# Schematic.net
KiCad netlist of a schematic drawn in EasyEDA
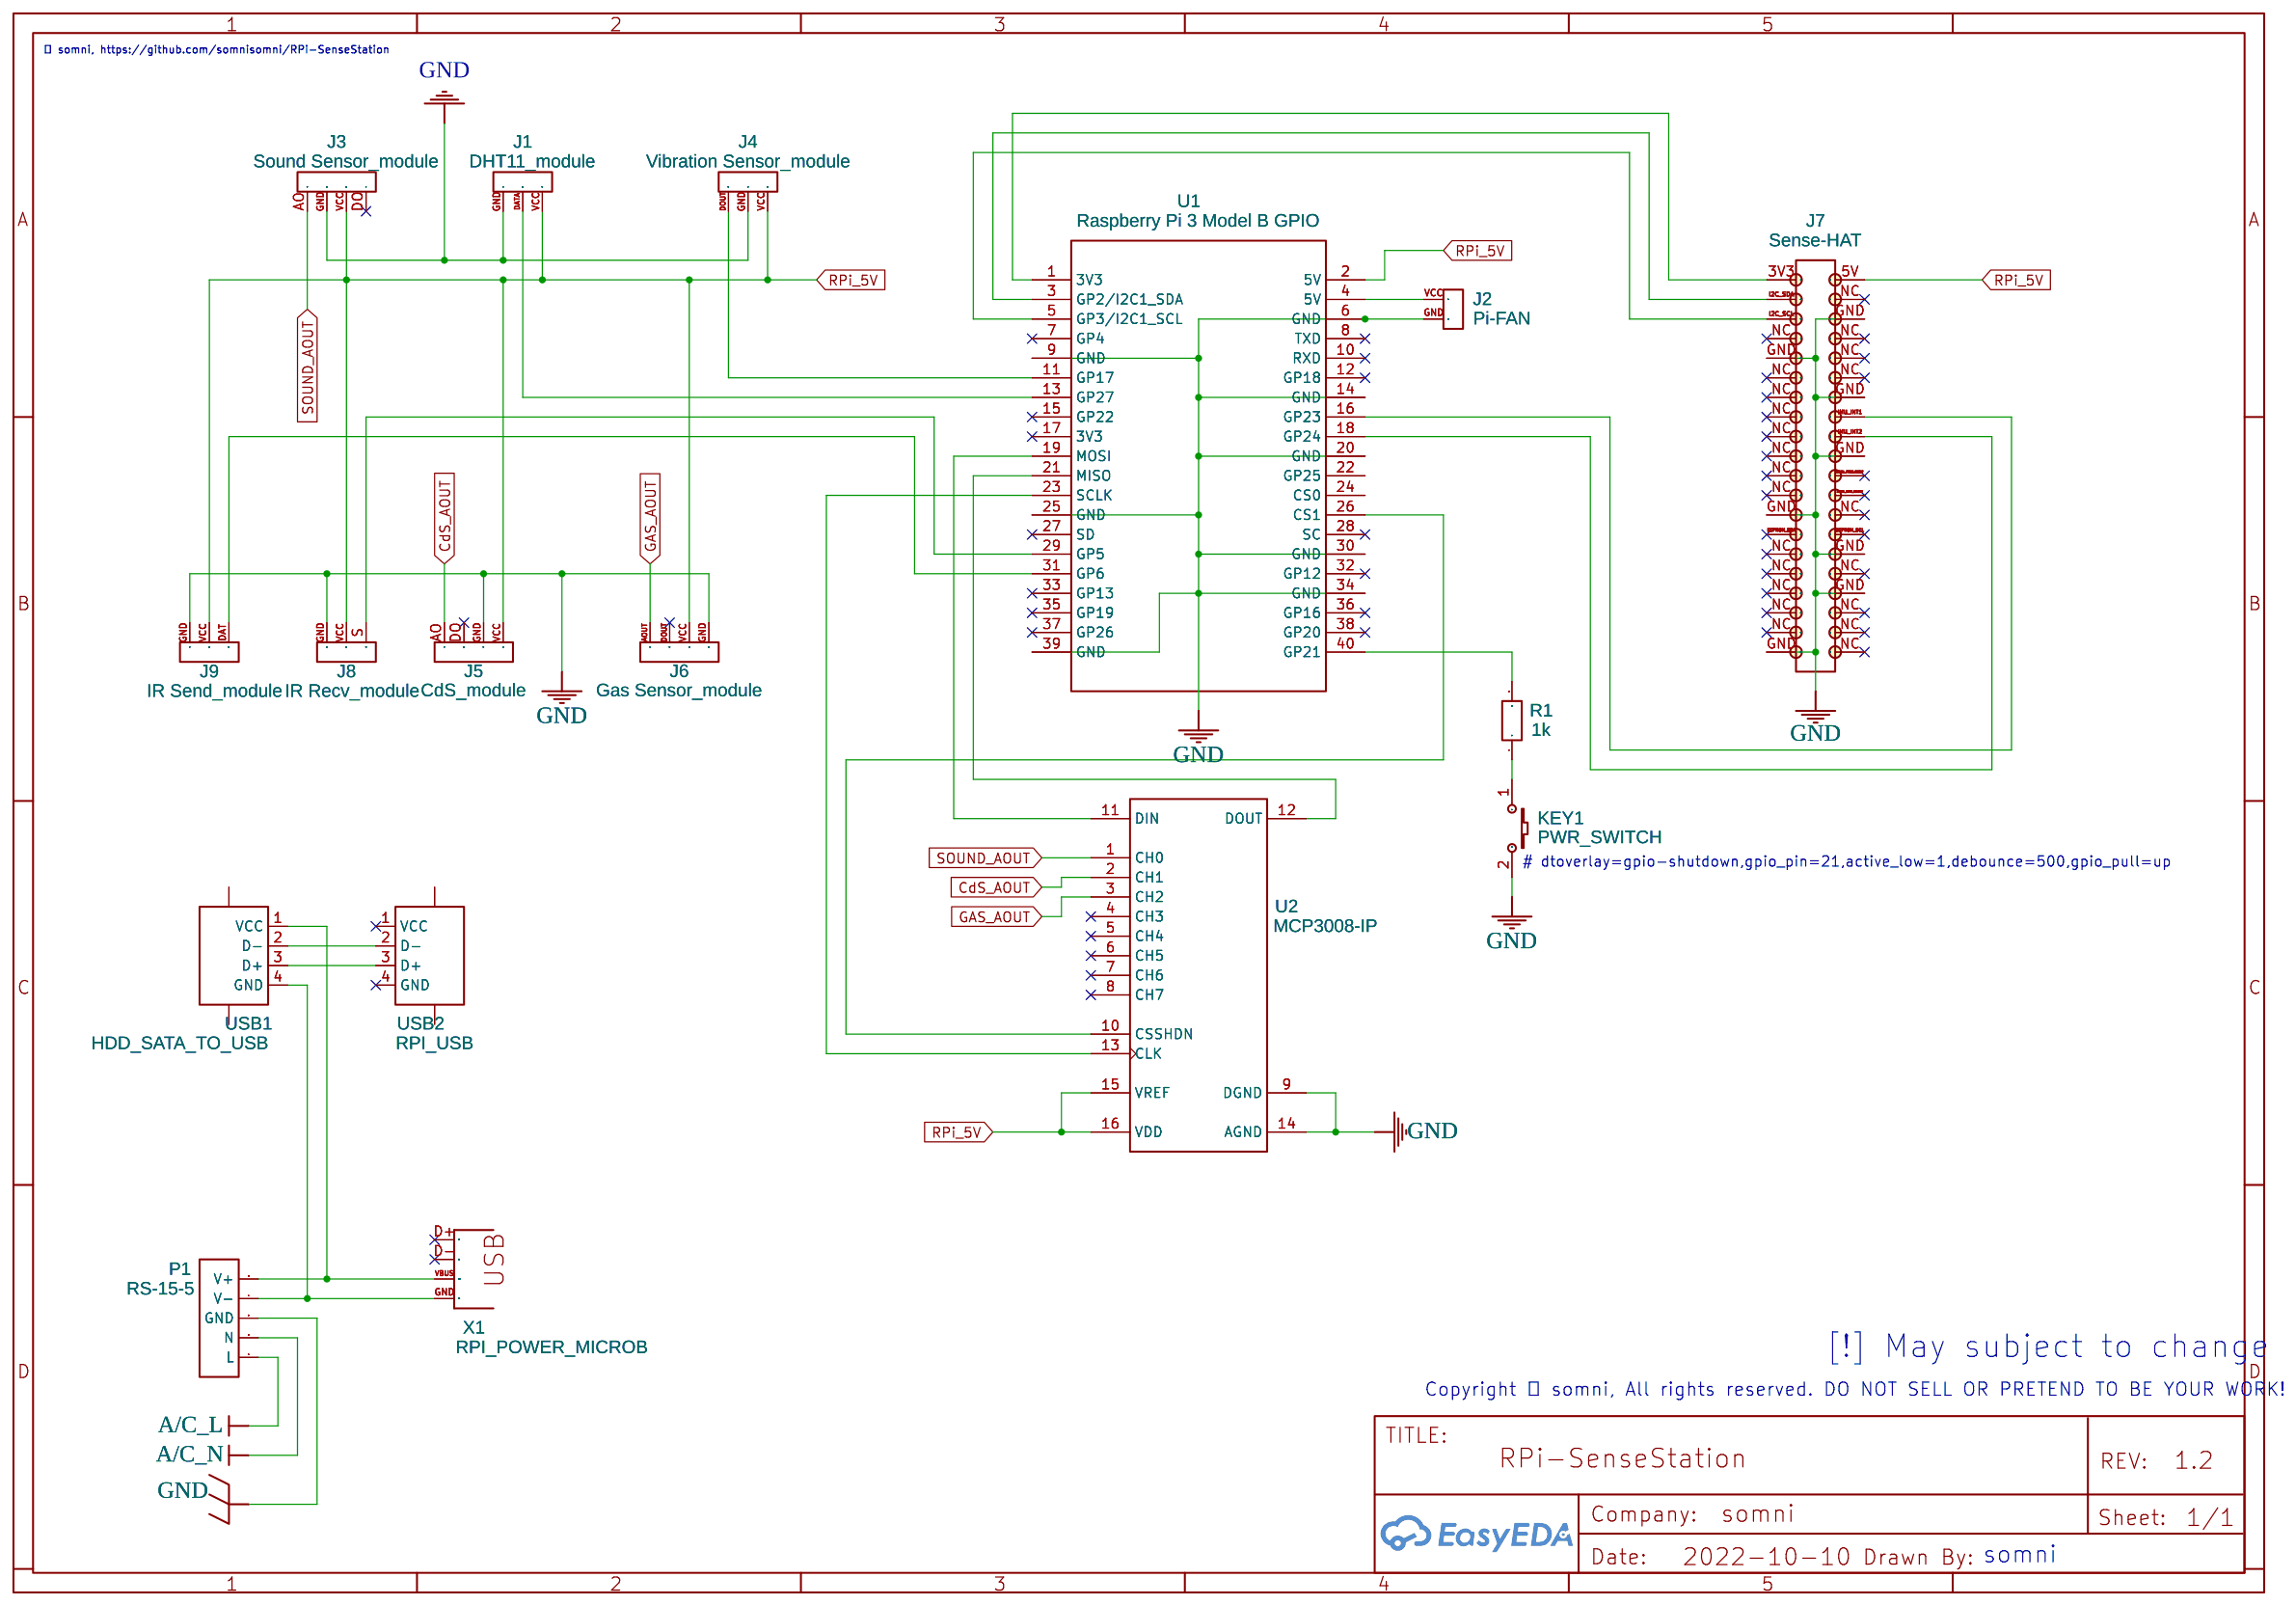
[diagram p0: schematic sheet]

(export (version "E")
  (design (tool "Eeschema 10.0.6"))
  (components
    (comp (ref "J1") (value "DHT11_module") (libsource (lib "") (part "HEADER_3_1")))
    (comp (ref "J2") (value "Pi-FAN") (libsource (lib "") (part "HEADER_2")))
    (comp (ref "J3") (value "Sound Sensor_module") (libsource (lib "") (part "HEADER_4_1")))
    (comp (ref "J4") (value "Vibration Sensor_module") (libsource (lib "") (part "HEADER_3_3")))
    (comp (ref "J5") (value "CdS_module") (libsource (lib "") (part "HEADER_4_2")))
    (comp (ref "J6") (value "Gas Sensor_module") (libsource (lib "") (part "HEADER_4")))
    (comp (ref "J7") (value "Sense-HAT") (libsource (lib "") (part "CON2X20")))
    (comp (ref "J8") (value "IR Recv_module") (libsource (lib "") (part "HEADER_3_2")))
    (comp (ref "J9") (value "IR Send_module") (libsource (lib "") (part "HEADER_3")))
    (comp (ref "KEY1")
      (value "PWR_SWITCH")
      (fields
        (field (name "BOM_Manufacturer Part") "K2-1107ST-A4SW-06")
        (field (name "BOM_Supplier Part") "C118141")
      )
      (libsource (lib "") (part "K2-3.6×6.1_SMD"))
    )
    (comp (ref "P1") (value "RS-15-5") (libsource (lib "") (part "RS-15-5")))
    (comp (ref "R1") (value "1k") (libsource (lib "") (part "R_0603_EU")))
    (comp (ref "U1")
      (value "Raspberry Pi 3 Model B GPIO")
      (fields (field (name "BOM_Supplier Part") "undefined"))
      (libsource (lib "") (part "Rasbperry Pi (2+) Shield Board fin"))
    )
    (comp (ref "U2") (value "MCP3008-IP") (libsource (lib "") (part "MCP3008-IP")))
    (comp (ref "USB1")
      (value "HDD_SATA_TO_USB")
      (fields (field (name "BOM_Manufacturer Part") "USB-05") (field (name "BOM_Supplier Part") "C112454"))
      (libsource (lib "") (part "USB-Type A_Male"))
    )
    (comp (ref "USB2")
      (value "RPI_USB")
      (fields (field (name "BOM_Manufacturer Part") "USB-05") (field (name "BOM_Supplier Part") "C112454"))
      (libsource (lib "") (part "USB-Type A_Male_1"))
    )
    (comp (ref "X1") (value "RPI_POWER_MICROB") (libsource (lib "") (part "USB-MICROB")))
  )
  (nets
    (net (code "1") (name "A{slash}C_L") (class "Default")
      (node (ref "P1") (pin "1") (pinfunction "L_1") (pintype "unspecified"))
    )
    (net (code "2") (name "A{slash}C_N") (class "Default")
      (node (ref "P1") (pin "2") (pinfunction "N_2") (pintype "unspecified"))
    )
    (net (code "3") (name "CdS_AOUT") (class "Default")
      (node (ref "J5") (pin "AO") (pinfunction "4_AO") (pintype "unspecified"))
      (node (ref "U2") (pin "2") (pinfunction "CH1_2") (pintype "unspecified"))
    )
    (net (code "4") (name "GAS_AOUT") (class "Default")
      (node (ref "J6") (pin "AOUT") (pinfunction "4_AOUT") (pintype "unspecified"))
      (node (ref "U2") (pin "3") (pinfunction "CH2_3") (pintype "unspecified"))
    )
    (net (code "5") (name "GND") (class "Default")
      (node (ref "J1") (pin "GND") (pinfunction "1_GND") (pintype "unspecified"))
      (node (ref "J2") (pin "GND") (pinfunction "2_GND") (pintype "unspecified"))
      (node (ref "J3") (pin "GND") (pinfunction "2_GND") (pintype "unspecified"))
      (node (ref "J4") (pin "GND") (pinfunction "2_GND") (pintype "unspecified"))
      (node (ref "J5") (pin "GND") (pinfunction "2_GND") (pintype "unspecified"))
      (node (ref "J6") (pin "GND") (pinfunction "1_GND") (pintype "unspecified"))
      (node (ref "J7") (pin "GND") (pinfunction "34_GND") (pintype "unspecified"))
      (node (ref "J8") (pin "GND") (pinfunction "1_GND") (pintype "unspecified"))
      (node (ref "J9") (pin "GND") (pinfunction "1_GND") (pintype "unspecified"))
      (node (ref "KEY1") (pin "2") (pinfunction "2_2") (pintype "unspecified"))
      (node (ref "P1") (pin "3") (pinfunction "GND_3") (pintype "unspecified"))
      (node (ref "U1") (pin "14") (pinfunction "GND_14") (pintype "unspecified"))
      (node (ref "U1") (pin "20") (pinfunction "GND_20") (pintype "unspecified"))
      (node (ref "U1") (pin "25") (pinfunction "GND_25") (pintype "unspecified"))
      (node (ref "U1") (pin "30") (pinfunction "GND_30") (pintype "unspecified"))
      (node (ref "U1") (pin "34") (pinfunction "GND_34") (pintype "unspecified"))
      (node (ref "U1") (pin "39") (pinfunction "GND_39") (pintype "unspecified"))
      (node (ref "U1") (pin "6") (pinfunction "GND_6") (pintype "unspecified"))
      (node (ref "U1") (pin "9") (pinfunction "GND_9") (pintype "unspecified"))
      (node (ref "U2") (pin "14") (pinfunction "AGND_14") (pintype "passive"))
      (node (ref "U2") (pin "9") (pinfunction "DGND_9") (pintype "passive"))
    )
    (net (code "6") (name "Net-(J1-2)") (class "Default")
      (node (ref "J1") (pin "DATA") (pinfunction "2_DATA") (pintype "unspecified"))
      (node (ref "U1") (pin "13") (pinfunction "GP27_13") (pintype "unspecified"))
    )
    (net (code "7") (name "Net-(J2-1)") (class "Default")
      (node (ref "J2") (pin "VCC") (pinfunction "1_VCC") (pintype "unspecified"))
      (node (ref "U1") (pin "4") (pinfunction "5V_4") (pintype "unspecified"))
    )
    (net (code "8") (name "Net-(J4-3)") (class "Default")
      (node (ref "J4") (pin "DOUT") (pinfunction "3_DOUT") (pintype "unspecified"))
      (node (ref "U1") (pin "11") (pinfunction "GP17_11") (pintype "unspecified"))
    )
    (net (code "9") (name "Net-(J7-1)") (class "Default")
      (node (ref "J7") (pin "3V3") (pinfunction "1_3V3") (pintype "unspecified"))
      (node (ref "U1") (pin "1") (pinfunction "3V3_1") (pintype "unspecified"))
    )
    (net (code "10") (name "Net-(J7-3)") (class "Default")
      (node (ref "J7") (pin "I2C_SDA") (pinfunction "3_I2C_SDA") (pintype "unspecified"))
      (node (ref "U1") (pin "3") (pinfunction "GP2/I2C1_SDA_3") (pintype "unspecified"))
    )
    (net (code "11") (name "Net-(J7-5)") (class "Default")
      (node (ref "J7") (pin "I2C_SCL") (pinfunction "5_I2C_SCL") (pintype "unspecified"))
      (node (ref "U1") (pin "5") (pinfunction "GP3/I2C1_SCL_5") (pintype "unspecified"))
    )
    (net (code "12") (name "Net-(J7-16)") (class "Default")
      (node (ref "J7") (pin "IMU_INT1") (pinfunction "16_IMU_INT1") (pintype "unspecified"))
      (node (ref "U1") (pin "16") (pinfunction "GP23_16") (pintype "unspecified"))
    )
    (net (code "13") (name "Net-(J7-18)") (class "Default")
      (node (ref "J7") (pin "IMU_INT2") (pinfunction "18_IMU_INT2") (pintype "unspecified"))
      (node (ref "U1") (pin "18") (pinfunction "GP24_18") (pintype "unspecified"))
    )
    (net (code "14") (name "Net-(J8-3)") (class "Default")
      (node (ref "J8") (pin "S") (pinfunction "3_S") (pintype "unspecified"))
      (node (ref "U1") (pin "29") (pinfunction "GP5_29") (pintype "unspecified"))
    )
    (net (code "15") (name "Net-(J9-3)") (class "Default")
      (node (ref "J9") (pin "DAT") (pinfunction "3_DAT") (pintype "unspecified"))
      (node (ref "U1") (pin "31") (pinfunction "GP6_31") (pintype "unspecified"))
    )
    (net (code "16") (name "Net-(KEY1-Pad1)") (class "Default")
      (node (ref "KEY1") (pin "1") (pinfunction "1_1") (pintype "unspecified"))
      (node (ref "R1") (pin "1") (pinfunction "1_1") (pintype "unspecified"))
    )
    (net (code "17") (name "Net-(P1-V+)") (class "Default")
      (node (ref "P1") (pin "5") (pinfunction "V+_5") (pintype "unspecified"))
      (node (ref "USB1") (pin "1") (pinfunction "VCC_1") (pintype "input"))
      (node (ref "X1") (pin "VBUS") (pinfunction "VBUS_VBUS") (pintype "unspecified"))
    )
    (net (code "18") (name "Net-(P1-V-)") (class "Default")
      (node (ref "P1") (pin "4") (pinfunction "V-_4") (pintype "unspecified"))
      (node (ref "USB1") (pin "4") (pinfunction "GND_4") (pintype "input"))
      (node (ref "X1") (pin "GND") (pinfunction "GND_GND") (pintype "unspecified"))
    )
    (net (code "19") (name "Net-(U1-CS1)") (class "Default")
      (node (ref "U1") (pin "26") (pinfunction "CS1_26") (pintype "unspecified"))
      (node (ref "U2") (pin "10") (pinfunction "CSSHDN_10") (pintype "unspecified"))
    )
    (net (code "20") (name "Net-(U1-GP21)") (class "Default")
      (node (ref "R1") (pin "2") (pinfunction "2_2") (pintype "unspecified"))
      (node (ref "U1") (pin "40") (pinfunction "GP21_40") (pintype "unspecified"))
    )
    (net (code "21") (name "Net-(U1-MISO)") (class "Default")
      (node (ref "U1") (pin "21") (pinfunction "MISO_21") (pintype "unspecified"))
      (node (ref "U2") (pin "12") (pinfunction "DOUT_12") (pintype "unspecified"))
    )
    (net (code "22") (name "Net-(U1-MOSI)") (class "Default")
      (node (ref "U1") (pin "19") (pinfunction "MOSI_19") (pintype "unspecified"))
      (node (ref "U2") (pin "11") (pinfunction "DIN_11") (pintype "unspecified"))
    )
    (net (code "23") (name "Net-(U1-SCLK)") (class "Default")
      (node (ref "U1") (pin "23") (pinfunction "SCLK_23") (pintype "unspecified"))
      (node (ref "U2") (pin "13") (pinfunction "CLK_13") (pintype "unspecified"))
    )
    (net (code "24") (name "Net-(USB1-D+)") (class "Default")
      (node (ref "USB1") (pin "3") (pinfunction "D+_3") (pintype "input"))
      (node (ref "USB2") (pin "3") (pinfunction "D+_3") (pintype "input"))
    )
    (net (code "25") (name "Net-(USB1-D-)") (class "Default")
      (node (ref "USB1") (pin "2") (pinfunction "D-_2") (pintype "input"))
      (node (ref "USB2") (pin "2") (pinfunction "D-_2") (pintype "input"))
    )
    (net (code "26") (name "RPi_5V") (class "Default")
      (node (ref "J1") (pin "VCC") (pinfunction "3_VCC") (pintype "unspecified"))
      (node (ref "J3") (pin "VCC") (pinfunction "3_VCC") (pintype "unspecified"))
      (node (ref "J4") (pin "VCC") (pinfunction "1_VCC") (pintype "unspecified"))
      (node (ref "J5") (pin "VCC") (pinfunction "1_VCC") (pintype "unspecified"))
      (node (ref "J6") (pin "VCC") (pinfunction "2_VCC") (pintype "unspecified"))
      (node (ref "J7") (pin "5V") (pinfunction "2_5V") (pintype "unspecified"))
      (node (ref "J8") (pin "VCC") (pinfunction "2_VCC") (pintype "unspecified"))
      (node (ref "J9") (pin "VCC") (pinfunction "2_VCC") (pintype "unspecified"))
      (node (ref "U1") (pin "2") (pinfunction "5V_2") (pintype "unspecified"))
      (node (ref "U2") (pin "15") (pinfunction "VREF_15") (pintype "unspecified"))
      (node (ref "U2") (pin "16") (pinfunction "VDD_16") (pintype "passive"))
    )
    (net (code "27") (name "SOUND_AOUT") (class "Default")
      (node (ref "J3") (pin "AO") (pinfunction "1_AO") (pintype "unspecified"))
      (node (ref "U2") (pin "1") (pinfunction "CH0_1") (pintype "unspecified"))
    )
    (net (code "28") (name "unconnected-(J3-4-PadDO)") (class "Default")
      (node (ref "J3") (pin "DO") (pinfunction "4_DO") (pintype "unspecified+no_connect"))
    )
    (net (code "29") (name "unconnected-(J5-3-PadDO)") (class "Default")
      (node (ref "J5") (pin "DO") (pinfunction "3_DO") (pintype "unspecified+no_connect"))
    )
    (net (code "30") (name "unconnected-(J6-3-PadDOUT)") (class "Default")
      (node (ref "J6") (pin "DOUT") (pinfunction "3_DOUT") (pintype "unspecified+no_connect"))
    )
    (net (code "31") (name "unconnected-(J7-4-PadNC)") (class "Default")
      (node (ref "J7") (pin "NC") (pinfunction "4_NC") (pintype "unspecified+no_connect"))
    )
    (net (code "32") (name "unconnected-(J7-7-PadNC)") (class "Default")
      (node (ref "J7") (pin "NC") (pinfunction "7_NC") (pintype "unspecified+no_connect"))
    )
    (net (code "33") (name "unconnected-(J7-8-PadNC)") (class "Default")
      (node (ref "J7") (pin "NC") (pinfunction "8_NC") (pintype "unspecified+no_connect"))
    )
    (net (code "34") (name "unconnected-(J7-10-PadNC)") (class "Default")
      (node (ref "J7") (pin "NC") (pinfunction "10_NC") (pintype "unspecified+no_connect"))
    )
    (net (code "35") (name "unconnected-(J7-11-PadNC)") (class "Default")
      (node (ref "J7") (pin "NC") (pinfunction "11_NC") (pintype "unspecified+no_connect"))
    )
    (net (code "36") (name "unconnected-(J7-12-PadNC)") (class "Default")
      (node (ref "J7") (pin "NC") (pinfunction "12_NC") (pintype "unspecified+no_connect"))
    )
    (net (code "37") (name "unconnected-(J7-13-PadNC)") (class "Default")
      (node (ref "J7") (pin "NC") (pinfunction "13_NC") (pintype "unspecified+no_connect"))
    )
    (net (code "38") (name "unconnected-(J7-15-PadNC)") (class "Default")
      (node (ref "J7") (pin "NC") (pinfunction "15_NC") (pintype "unspecified+no_connect"))
    )
    (net (code "39") (name "unconnected-(J7-17-PadNC)") (class "Default")
      (node (ref "J7") (pin "NC") (pinfunction "17_NC") (pintype "unspecified+no_connect"))
    )
    (net (code "40") (name "unconnected-(J7-19-PadNC)") (class "Default")
      (node (ref "J7") (pin "NC") (pinfunction "19_NC") (pintype "unspecified+no_connect"))
    )
    (net (code "41") (name "unconnected-(J7-21-PadNC)") (class "Default")
      (node (ref "J7") (pin "NC") (pinfunction "21_NC") (pintype "unspecified+no_connect"))
    )
    (net (code "42") (name "unconnected-(J7-22-PadATMEL_PROG_RESET)") (class "Default")
      (node (ref "J7") (pin "ATMEL_PROG_RESET") (pinfunction "22_ATMEL_PROG_RESET") (pintype "unspecified+no_connect"))
    )
    (net (code "43") (name "unconnected-(J7-23-PadNC)") (class "Default")
      (node (ref "J7") (pin "NC") (pinfunction "23_NC") (pintype "unspecified+no_connect"))
    )
    (net (code "44") (name "unconnected-(J7-24-PadATMEL_CHIP_SELECT)") (class "Default")
      (node (ref "J7") (pin "ATMEL_CHIP_SELECT") (pinfunction "24_ATMEL_CHIP_SELECT") (pintype "unspecified+no_connect"))
    )
    (net (code "45") (name "unconnected-(J7-26-PadNC)") (class "Default")
      (node (ref "J7") (pin "NC") (pinfunction "26_NC") (pintype "unspecified+no_connect"))
    )
    (net (code "46") (name "unconnected-(J7-27-PadEEPROM_SDA)") (class "Default")
      (node (ref "J7") (pin "EEPROM_SDA") (pinfunction "27_EEPROM_SDA") (pintype "unspecified+no_connect"))
    )
    (net (code "47") (name "unconnected-(J7-28-PadEEPROM_SCL)") (class "Default")
      (node (ref "J7") (pin "EEPROM_SCL") (pinfunction "28_EEPROM_SCL") (pintype "unspecified+no_connect"))
    )
    (net (code "48") (name "unconnected-(J7-29-PadNC)") (class "Default")
      (node (ref "J7") (pin "NC") (pinfunction "29_NC") (pintype "unspecified+no_connect"))
    )
    (net (code "49") (name "unconnected-(J7-31-PadNC)") (class "Default")
      (node (ref "J7") (pin "NC") (pinfunction "31_NC") (pintype "unspecified+no_connect"))
    )
    (net (code "50") (name "unconnected-(J7-32-PadNC)") (class "Default")
      (node (ref "J7") (pin "NC") (pinfunction "32_NC") (pintype "unspecified+no_connect"))
    )
    (net (code "51") (name "unconnected-(J7-33-PadNC)") (class "Default")
      (node (ref "J7") (pin "NC") (pinfunction "33_NC") (pintype "unspecified+no_connect"))
    )
    (net (code "52") (name "unconnected-(J7-35-PadNC)") (class "Default")
      (node (ref "J7") (pin "NC") (pinfunction "35_NC") (pintype "unspecified+no_connect"))
    )
    (net (code "53") (name "unconnected-(J7-36-PadNC)") (class "Default")
      (node (ref "J7") (pin "NC") (pinfunction "36_NC") (pintype "unspecified+no_connect"))
    )
    (net (code "54") (name "unconnected-(J7-37-PadNC)") (class "Default")
      (node (ref "J7") (pin "NC") (pinfunction "37_NC") (pintype "unspecified+no_connect"))
    )
    (net (code "55") (name "unconnected-(J7-38-PadNC)") (class "Default")
      (node (ref "J7") (pin "NC") (pinfunction "38_NC") (pintype "unspecified+no_connect"))
    )
    (net (code "56") (name "unconnected-(J7-40-PadNC)") (class "Default")
      (node (ref "J7") (pin "NC") (pinfunction "40_NC") (pintype "unspecified+no_connect"))
    )
    (net (code "57") (name "unconnected-(U1-3V3-Pad17)") (class "Default")
      (node (ref "U1") (pin "17") (pinfunction "3V3_17") (pintype "unspecified+no_connect"))
    )
    (net (code "58") (name "unconnected-(U1-CS0-Pad24)") (class "Default")
      (node (ref "U1") (pin "24") (pinfunction "CS0_24") (pintype "unspecified"))
    )
    (net (code "59") (name "unconnected-(U1-GP4-Pad7)") (class "Default")
      (node (ref "U1") (pin "7") (pinfunction "GP4_7") (pintype "unspecified+no_connect"))
    )
    (net (code "60") (name "unconnected-(U1-GP12-Pad32)") (class "Default")
      (node (ref "U1") (pin "32") (pinfunction "GP12_32") (pintype "unspecified+no_connect"))
    )
    (net (code "61") (name "unconnected-(U1-GP13-Pad33)") (class "Default")
      (node (ref "U1") (pin "33") (pinfunction "GP13_33") (pintype "unspecified+no_connect"))
    )
    (net (code "62") (name "unconnected-(U1-GP16-Pad36)") (class "Default")
      (node (ref "U1") (pin "36") (pinfunction "GP16_36") (pintype "unspecified+no_connect"))
    )
    (net (code "63") (name "unconnected-(U1-GP18-Pad12)") (class "Default")
      (node (ref "U1") (pin "12") (pinfunction "GP18_12") (pintype "unspecified+no_connect"))
    )
    (net (code "64") (name "unconnected-(U1-GP19-Pad35)") (class "Default")
      (node (ref "U1") (pin "35") (pinfunction "GP19_35") (pintype "unspecified+no_connect"))
    )
    (net (code "65") (name "unconnected-(U1-GP20-Pad38)") (class "Default")
      (node (ref "U1") (pin "38") (pinfunction "GP20_38") (pintype "unspecified+no_connect"))
    )
    (net (code "66") (name "unconnected-(U1-GP22-Pad15)") (class "Default")
      (node (ref "U1") (pin "15") (pinfunction "GP22_15") (pintype "unspecified+no_connect"))
    )
    (net (code "67") (name "unconnected-(U1-GP25-Pad22)") (class "Default")
      (node (ref "U1") (pin "22") (pinfunction "GP25_22") (pintype "unspecified"))
    )
    (net (code "68") (name "unconnected-(U1-GP26-Pad37)") (class "Default")
      (node (ref "U1") (pin "37") (pinfunction "GP26_37") (pintype "unspecified+no_connect"))
    )
    (net (code "69") (name "unconnected-(U1-RXD-Pad10)") (class "Default")
      (node (ref "U1") (pin "10") (pinfunction "RXD_10") (pintype "unspecified+no_connect"))
    )
    (net (code "70") (name "unconnected-(U1-SC-Pad28)") (class "Default")
      (node (ref "U1") (pin "28") (pinfunction "SC_28") (pintype "unspecified+no_connect"))
    )
    (net (code "71") (name "unconnected-(U1-SD-Pad27)") (class "Default")
      (node (ref "U1") (pin "27") (pinfunction "SD_27") (pintype "unspecified+no_connect"))
    )
    (net (code "72") (name "unconnected-(U1-TXD-Pad8)") (class "Default")
      (node (ref "U1") (pin "8") (pinfunction "TXD_8") (pintype "unspecified+no_connect"))
    )
    (net (code "73") (name "unconnected-(U2-CH3-Pad4)") (class "Default")
      (node (ref "U2") (pin "4") (pinfunction "CH3_4") (pintype "unspecified+no_connect"))
    )
    (net (code "74") (name "unconnected-(U2-CH4-Pad5)") (class "Default")
      (node (ref "U2") (pin "5") (pinfunction "CH4_5") (pintype "unspecified+no_connect"))
    )
    (net (code "75") (name "unconnected-(U2-CH5-Pad6)") (class "Default")
      (node (ref "U2") (pin "6") (pinfunction "CH5_6") (pintype "unspecified+no_connect"))
    )
    (net (code "76") (name "unconnected-(U2-CH6-Pad7)") (class "Default")
      (node (ref "U2") (pin "7") (pinfunction "CH6_7") (pintype "unspecified+no_connect"))
    )
    (net (code "77") (name "unconnected-(U2-CH7-Pad8)") (class "Default")
      (node (ref "U2") (pin "8") (pinfunction "CH7_8") (pintype "unspecified+no_connect"))
    )
    (net (code "78") (name "unconnected-(USB1-Pad)") (class "Default")
      (node (ref "USB1") (pin "") (pintype "unspecified"))
    )
    (net (code "79") (name "unconnected-(USB1-Pad)_1") (class "Default")
      (node (ref "USB1") (pin "") (pintype "unspecified"))
    )
    (net (code "80") (name "unconnected-(USB2-GND-Pad4)") (class "Default")
      (node (ref "USB2") (pin "4") (pinfunction "GND_4") (pintype "input+no_connect"))
    )
    (net (code "81") (name "unconnected-(USB2-Pad)") (class "Default")
      (node (ref "USB2") (pin "") (pintype "unspecified"))
    )
    (net (code "82") (name "unconnected-(USB2-Pad)_1") (class "Default")
      (node (ref "USB2") (pin "") (pintype "unspecified"))
    )
    (net (code "83") (name "unconnected-(USB2-VCC-Pad1)") (class "Default")
      (node (ref "USB2") (pin "1") (pinfunction "VCC_1") (pintype "input+no_connect"))
    )
    (net (code "84") (name "unconnected-(X1-PadD+)") (class "Default")
      (node (ref "X1") (pin "D+") (pinfunction "D+_D+") (pintype "unspecified+no_connect"))
    )
    (net (code "85") (name "unconnected-(X1-PadD-)") (class "Default")
      (node (ref "X1") (pin "D-") (pinfunction "D-_D-") (pintype "unspecified+no_connect"))
    )
  )
)
